# untitled.net
KiCad netlist of a schematic drawn in EAGLE
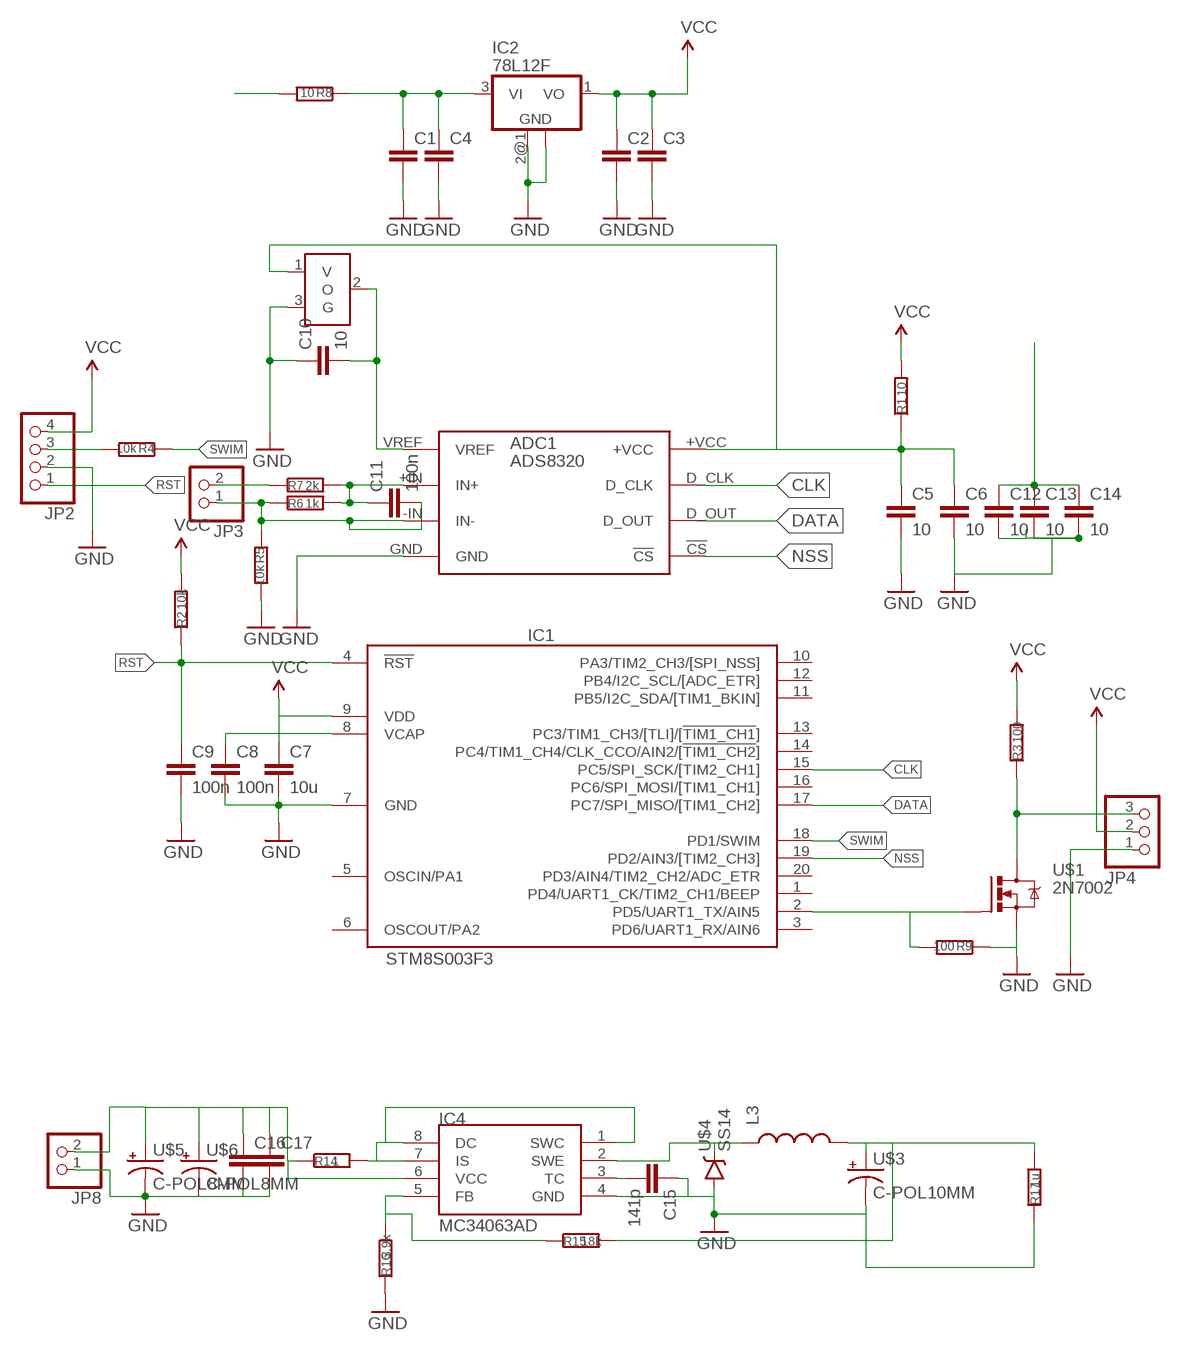
[diagram p0: schematic, sheet 1]

(export (version "E")
  (design (tool "Eeschema 10.0.6"))
  (components
    (comp (ref "ADC1")
      (value "ADS8320")
      (footprint "eagle-import:S-PDSO-G8")
      (libsource (lib "eagle-import") (part "ADS8320"))
    )
    (comp (ref "C1")
      (value "CC0805")
      (footprint "eagle-import:C0805")
      (libsource (lib "eagle-import") (part "CC0805"))
    )
    (comp (ref "C2")
      (value "CC0805")
      (footprint "eagle-import:C0805")
      (libsource (lib "eagle-import") (part "CC0805"))
    )
    (comp (ref "C3")
      (value "CC0805")
      (footprint "eagle-import:C0805")
      (libsource (lib "eagle-import") (part "CC0805"))
    )
    (comp (ref "C4")
      (value "CC0805")
      (footprint "eagle-import:C0805")
      (libsource (lib "eagle-import") (part "CC0805"))
    )
    (comp (ref "C5")
      (value "10")
      (footprint "eagle-import:C0805")
      (libsource (lib "eagle-import") (part "CC0805"))
    )
    (comp (ref "C6")
      (value "10")
      (footprint "eagle-import:C0805")
      (libsource (lib "eagle-import") (part "CC0805"))
    )
    (comp (ref "C7")
      (value "10u")
      (footprint "eagle-import:C0805")
      (libsource (lib "eagle-import") (part "CC0805"))
    )
    (comp (ref "C8")
      (value "100n")
      (footprint "eagle-import:C0603")
      (libsource (lib "eagle-import") (part "CC0603"))
    )
    (comp (ref "C9")
      (value "100n")
      (footprint "eagle-import:C0603")
      (libsource (lib "eagle-import") (part "CC0603"))
    )
    (comp (ref "C10")
      (value "10")
      (footprint "eagle-import:C0805")
      (libsource (lib "eagle-import") (part "CC0805"))
    )
    (comp (ref "C11")
      (value "100n")
      (footprint "eagle-import:C0603")
      (libsource (lib "eagle-import") (part "CC0603"))
    )
    (comp (ref "C12")
      (value "10")
      (footprint "eagle-import:C0805")
      (libsource (lib "eagle-import") (part "CC0805"))
    )
    (comp (ref "C13")
      (value "10")
      (footprint "eagle-import:C0805")
      (libsource (lib "eagle-import") (part "CC0805"))
    )
    (comp (ref "C14")
      (value "10")
      (footprint "eagle-import:C0805")
      (libsource (lib "eagle-import") (part "CC0805"))
    )
    (comp (ref "C15")
      (value "141p")
      (footprint "eagle-import:C0603")
      (libsource (lib "eagle-import") (part "CC0603"))
    )
    (comp (ref "C16")
      (value "CC0805")
      (footprint "eagle-import:C0805")
      (libsource (lib "eagle-import") (part "CC0805"))
    )
    (comp (ref "C17")
      (value "CC0805")
      (footprint "eagle-import:C0805")
      (libsource (lib "eagle-import") (part "CC0805"))
    )
    (comp (ref "IC1")
      (value "STM8S003F3")
      (footprint "eagle-import:TSSOP20")
      (libsource (lib "eagle-import") (part "STM8S003F3"))
    )
    (comp (ref "IC2")
      (value "78L12F")
      (footprint "eagle-import:SOT89")
      (libsource (lib "eagle-import") (part "78LF12"))
    )
    (comp (ref "IC4")
      (value "MC34063AD")
      (footprint "eagle-import:SOIC8")
      (libsource (lib "eagle-import") (part "MC34063AD"))
    )
    (comp (ref "JP2")
      (value "PINHD-1X04_2.54")
      (footprint "eagle-import:1X04")
      (libsource (lib "eagle-import") (part "PINHD-1X04_2.54"))
    )
    (comp (ref "JP3")
      (value "PINHD-1X2")
      (footprint "eagle-import:1X02")
      (libsource (lib "eagle-import") (part "PINHD-1X2"))
    )
    (comp (ref "JP4")
      (value "PINHD-1X03_2.54")
      (footprint "eagle-import:1X03")
      (libsource (lib "eagle-import") (part "PINHD-1X03_2.54"))
    )
    (comp (ref "JP8")
      (value "PINHD-1X02_2.54")
      (footprint "eagle-import:1X02")
      (libsource (lib "eagle-import") (part "PINHD-1X02_2.54"))
    )
    (comp (ref "L3")
      (value "INDUCTORSRU1038")
      (footprint "eagle-import:SRU1038")
      (libsource (lib "eagle-import") (part "INDUCTORSRU1038"))
    )
    (comp (ref "R1")
      (value "10")
      (footprint "eagle-import:0603")
      (libsource (lib "eagle-import") (part "R0603"))
    )
    (comp (ref "R2")
      (value "10k")
      (footprint "eagle-import:0603")
      (libsource (lib "eagle-import") (part "R0603"))
    )
    (comp (ref "R3")
      (value "100")
      (footprint "eagle-import:0603")
      (libsource (lib "eagle-import") (part "R0603"))
    )
    (comp (ref "R4")
      (value "10k")
      (footprint "eagle-import:0603")
      (libsource (lib "eagle-import") (part "R0603"))
    )
    (comp (ref "R5")
      (value "10k")
      (footprint "eagle-import:0603")
      (libsource (lib "eagle-import") (part "R0603"))
    )
    (comp (ref "R6")
      (value "1k")
      (footprint "eagle-import:0603")
      (libsource (lib "eagle-import") (part "R0603"))
    )
    (comp (ref "R7")
      (value "2k")
      (footprint "eagle-import:0603")
      (libsource (lib "eagle-import") (part "R0603"))
    )
    (comp (ref "R8")
      (value "10")
      (footprint "eagle-import:0603")
      (libsource (lib "eagle-import") (part "R0603"))
    )
    (comp (ref "R9")
      (value "100")
      (footprint "eagle-import:0603")
      (libsource (lib "eagle-import") (part "R0603"))
    )
    (comp (ref "R14")
      (value "1")
      (footprint "eagle-import:R0805")
      (libsource (lib "eagle-import") (part "R0805"))
    )
    (comp (ref "R15")
      (value "18k")
      (footprint "eagle-import:0603")
      (libsource (lib "eagle-import") (part "R0603"))
    )
    (comp (ref "R16")
      (value "3.9k")
      (footprint "eagle-import:0603")
      (libsource (lib "eagle-import") (part "R0603"))
    )
    (comp (ref "R17")
      (value "1u")
      (footprint "eagle-import:R0805")
      (libsource (lib "eagle-import") (part "R0805"))
    )
    (comp (ref "U$1")
      (value "2N7002")
      (footprint "eagle-import:SOT23")
      (libsource (lib "eagle-import") (part "2N7002"))
    )
    (comp (ref "U$2")
      (value "REF3025")
      (footprint "eagle-import:SOT23")
      (libsource (lib "eagle-import") (part "REF3025"))
    )
    (comp (ref "U$3")
      (value "C-POL10MM")
      (footprint "eagle-import:PCAP10")
      (libsource (lib "eagle-import") (part "C-POL10MM"))
    )
    (comp (ref "U$4")
      (value "SS14")
      (footprint "eagle-import:SMA-DIODE")
      (libsource (lib "eagle-import") (part "SS14"))
    )
    (comp (ref "U$5")
      (value "C-POL8MM")
      (footprint "eagle-import:PCAP8")
      (libsource (lib "eagle-import") (part "C-POL8MM"))
    )
    (comp (ref "U$6")
      (value "C-POL8MM")
      (footprint "eagle-import:PCAP8")
      (libsource (lib "eagle-import") (part "C-POL8MM"))
    )
  )
  (nets
    (net (code "1") (name "/N$2") (class "Default")
      (node (ref "C1") (pin "1") (pinfunction "1_1") (pintype "passive"))
      (node (ref "C12") (pin "1") (pinfunction "1_1") (pintype "passive"))
      (node (ref "C13") (pin "1") (pinfunction "1_1") (pintype "passive"))
      (node (ref "C14") (pin "1") (pinfunction "1_1") (pintype "passive"))
      (node (ref "C4") (pin "1") (pinfunction "1_1") (pintype "passive"))
      (node (ref "IC2") (pin "3") (pinfunction "VI_3") (pintype "input"))
      (node (ref "L3") (pin "2") (pinfunction "2_2") (pintype "passive"))
      (node (ref "R15") (pin "2") (pinfunction "2_2") (pintype "passive"))
      (node (ref "R17") (pin "2") (pinfunction "2_2") (pintype "passive"))
      (node (ref "R8") (pin "1") (pinfunction "1_1") (pintype "passive"))
      (node (ref "U$3") (pin "P$1") (pinfunction "+_P$1") (pintype "passive"))
    )
    (net (code "2") (name "CLK") (class "Default")
      (node (ref "ADC1") (pin "D_CLK") (pinfunction "D_CLK_D_CLK") (pintype "input"))
      (node (ref "IC1") (pin "15") (pinfunction "PC5/SPI_SCK/[TIM2_CH1]_15") (pintype "bidirectional"))
    )
    (net (code "3") (name "DATA") (class "Default")
      (node (ref "ADC1") (pin "D_OUT") (pinfunction "D_OUT_D_OUT") (pintype "output"))
      (node (ref "IC1") (pin "17") (pinfunction "PC7/SPI_MISO/[TIM1_CH2]_17") (pintype "bidirectional"))
    )
    (net (code "4") (name "GND") (class "Default")
      (node (ref "ADC1") (pin "GND") (pinfunction "GND_GND") (pintype "power_in"))
      (node (ref "C1") (pin "2") (pinfunction "2_2") (pintype "passive"))
      (node (ref "C10") (pin "1") (pinfunction "1_1") (pintype "passive"))
      (node (ref "C12") (pin "2") (pinfunction "2_2") (pintype "passive"))
      (node (ref "C13") (pin "2") (pinfunction "2_2") (pintype "passive"))
      (node (ref "C14") (pin "2") (pinfunction "2_2") (pintype "passive"))
      (node (ref "C15") (pin "1") (pinfunction "1_1") (pintype "passive"))
      (node (ref "C16") (pin "2") (pinfunction "2_2") (pintype "passive"))
      (node (ref "C17") (pin "2") (pinfunction "2_2") (pintype "passive"))
      (node (ref "C2") (pin "2") (pinfunction "2_2") (pintype "passive"))
      (node (ref "C3") (pin "2") (pinfunction "2_2") (pintype "passive"))
      (node (ref "C4") (pin "2") (pinfunction "2_2") (pintype "passive"))
      (node (ref "C5") (pin "2") (pinfunction "2_2") (pintype "passive"))
      (node (ref "C6") (pin "2") (pinfunction "2_2") (pintype "passive"))
      (node (ref "C7") (pin "2") (pinfunction "2_2") (pintype "passive"))
      (node (ref "C8") (pin "2") (pinfunction "2_2") (pintype "passive"))
      (node (ref "C9") (pin "2") (pinfunction "2_2") (pintype "passive"))
      (node (ref "IC1") (pin "7") (pinfunction "GND_7") (pintype "power_in"))
      (node (ref "IC2") (pin "2") (pinfunction "GND_2") (pintype "passive"))
      (node (ref "IC2") (pin "2@1") (pinfunction "GND_2@1") (pintype "passive"))
      (node (ref "IC4") (pin "4") (pinfunction "GND_4") (pintype "passive"))
      (node (ref "JP2") (pin "2") (pinfunction "2_2") (pintype "passive"))
      (node (ref "JP4") (pin "1") (pinfunction "1_1") (pintype "passive"))
      (node (ref "JP8") (pin "1") (pinfunction "1_1") (pintype "passive"))
      (node (ref "R16") (pin "1") (pinfunction "1_1") (pintype "passive"))
      (node (ref "R17") (pin "1") (pinfunction "1_1") (pintype "passive"))
      (node (ref "R5") (pin "2") (pinfunction "2_2") (pintype "passive"))
      (node (ref "R9") (pin "1") (pinfunction "1_1") (pintype "passive"))
      (node (ref "U$1") (pin "2") (pinfunction "S_2") (pintype "passive"))
      (node (ref "U$2") (pin "3") (pinfunction "G_3") (pintype "bidirectional"))
      (node (ref "U$3") (pin "P$2") (pinfunction "-_P$2") (pintype "passive"))
      (node (ref "U$4") (pin "A") (pinfunction "A_A") (pintype "passive"))
      (node (ref "U$5") (pin "P$2") (pinfunction "-_P$2") (pintype "passive"))
      (node (ref "U$6") (pin "P$2") (pinfunction "-_P$2") (pintype "passive"))
    )
    (net (code "5") (name "NSS") (class "Default")
      (node (ref "ADC1") (pin "!CS") (pinfunction "~{CS}_!CS") (pintype "input"))
      (node (ref "IC1") (pin "19") (pinfunction "PD2/AIN3/[TIM2_CH3]_19") (pintype "bidirectional"))
    )
    (net (code "6") (name "Net-(ADC1-IN+)") (class "Default")
      (node (ref "ADC1") (pin "+IN") (pinfunction "IN+_+IN") (pintype "input"))
      (node (ref "C11") (pin "1") (pinfunction "1_1") (pintype "passive"))
      (node (ref "R6") (pin "2") (pinfunction "2_2") (pintype "passive"))
      (node (ref "R7") (pin "2") (pinfunction "2_2") (pintype "passive"))
    )
    (net (code "7") (name "Net-(ADC1-IN-)") (class "Default")
      (node (ref "ADC1") (pin "-IN") (pinfunction "IN-_-IN") (pintype "input"))
      (node (ref "C11") (pin "2") (pinfunction "2_2") (pintype "passive"))
      (node (ref "JP3") (pin "1") (pinfunction "1_1") (pintype "passive"))
      (node (ref "R5") (pin "1") (pinfunction "1_1") (pintype "passive"))
      (node (ref "R6") (pin "1") (pinfunction "1_1") (pintype "passive"))
    )
    (net (code "8") (name "Net-(IC1-PD5{slash}UART1_TX{slash}AIN5)") (class "Default")
      (node (ref "IC1") (pin "2") (pinfunction "PD5/UART1_TX/AIN5_2") (pintype "bidirectional"))
      (node (ref "R9") (pin "2") (pinfunction "2_2") (pintype "passive"))
      (node (ref "U$1") (pin "1") (pinfunction "G_1") (pintype "passive"))
    )
    (net (code "9") (name "Net-(IC1-VCAP)") (class "Default")
      (node (ref "C8") (pin "1") (pinfunction "1_1") (pintype "passive"))
      (node (ref "IC1") (pin "8") (pinfunction "VCAP_8") (pintype "power_in"))
    )
    (net (code "10") (name "Net-(IC4-DC)") (class "Default")
      (node (ref "IC4") (pin "1") (pinfunction "SWC_1") (pintype "passive"))
      (node (ref "IC4") (pin "7") (pinfunction "IS_7") (pintype "passive"))
      (node (ref "IC4") (pin "8") (pinfunction "DC_8") (pintype "passive"))
      (node (ref "R14") (pin "2") (pinfunction "2_2") (pintype "passive"))
    )
    (net (code "11") (name "Net-(IC4-FB)") (class "Default")
      (node (ref "IC4") (pin "5") (pinfunction "FB_5") (pintype "passive"))
      (node (ref "R15") (pin "1") (pinfunction "1_1") (pintype "passive"))
      (node (ref "R16") (pin "2") (pinfunction "2_2") (pintype "passive"))
    )
    (net (code "12") (name "Net-(IC4-SWE)") (class "Default")
      (node (ref "IC4") (pin "2") (pinfunction "SWE_2") (pintype "passive"))
      (node (ref "L3") (pin "1") (pinfunction "1_1") (pintype "passive"))
      (node (ref "U$4") (pin "C") (pinfunction "C_C") (pintype "passive"))
    )
    (net (code "13") (name "Net-(IC4-TC)") (class "Default")
      (node (ref "C15") (pin "2") (pinfunction "2_2") (pintype "passive"))
      (node (ref "IC4") (pin "3") (pinfunction "TC_3") (pintype "passive"))
    )
    (net (code "14") (name "Net-(IC4-VCC)") (class "Default")
      (node (ref "C16") (pin "1") (pinfunction "1_1") (pintype "passive"))
      (node (ref "C17") (pin "1") (pinfunction "1_1") (pintype "passive"))
      (node (ref "IC4") (pin "6") (pinfunction "VCC_6") (pintype "passive"))
      (node (ref "JP8") (pin "2") (pinfunction "2_2") (pintype "passive"))
      (node (ref "R14") (pin "1") (pinfunction "1_1") (pintype "passive"))
      (node (ref "U$5") (pin "P$1") (pinfunction "+_P$1") (pintype "passive"))
      (node (ref "U$6") (pin "P$1") (pinfunction "+_P$1") (pintype "passive"))
    )
    (net (code "15") (name "Net-(JP2-Pad3)") (class "Default")
      (node (ref "JP2") (pin "3") (pinfunction "3_3") (pintype "passive"))
      (node (ref "R4") (pin "2") (pinfunction "2_2") (pintype "passive"))
    )
    (net (code "16") (name "Net-(JP3-Pad2)") (class "Default")
      (node (ref "JP3") (pin "2") (pinfunction "2_2") (pintype "passive"))
      (node (ref "R7") (pin "1") (pinfunction "1_1") (pintype "passive"))
    )
    (net (code "17") (name "Net-(U$1-D)") (class "Default")
      (node (ref "JP4") (pin "3") (pinfunction "3_3") (pintype "passive"))
      (node (ref "R3") (pin "1") (pinfunction "1_1") (pintype "passive"))
      (node (ref "U$1") (pin "3") (pinfunction "D_3") (pintype "passive"))
    )
    (net (code "18") (name "Net-(U$2-O)") (class "Default")
      (node (ref "ADC1") (pin "VREF") (pinfunction "VREF_VREF") (pintype "input"))
      (node (ref "C10") (pin "2") (pinfunction "2_2") (pintype "passive"))
      (node (ref "U$2") (pin "2") (pinfunction "O_2") (pintype "bidirectional"))
    )
    (net (code "19") (name "Net-(U$2-V)") (class "Default")
      (node (ref "ADC1") (pin "+VCC") (pinfunction "+VCC_+VCC") (pintype "power_in"))
      (node (ref "C5") (pin "1") (pinfunction "1_1") (pintype "passive"))
      (node (ref "C6") (pin "1") (pinfunction "1_1") (pintype "passive"))
      (node (ref "R1") (pin "1") (pinfunction "1_1") (pintype "passive"))
      (node (ref "U$2") (pin "1") (pinfunction "V_1") (pintype "bidirectional"))
    )
    (net (code "20") (name "RST") (class "Default")
      (node (ref "C9") (pin "1") (pinfunction "1_1") (pintype "passive"))
      (node (ref "IC1") (pin "4") (pinfunction "~{RST}_4") (pintype "input"))
      (node (ref "JP2") (pin "1") (pinfunction "1_1") (pintype "passive"))
      (node (ref "R2") (pin "1") (pinfunction "1_1") (pintype "passive"))
    )
    (net (code "21") (name "SWIM") (class "Default")
      (node (ref "IC1") (pin "18") (pinfunction "PD1/SWIM_18") (pintype "bidirectional"))
      (node (ref "R4") (pin "1") (pinfunction "1_1") (pintype "passive"))
    )
    (net (code "22") (name "VCC") (class "Default")
      (node (ref "C2") (pin "1") (pinfunction "1_1") (pintype "passive"))
      (node (ref "C3") (pin "1") (pinfunction "1_1") (pintype "passive"))
      (node (ref "C7") (pin "1") (pinfunction "1_1") (pintype "passive"))
      (node (ref "IC1") (pin "9") (pinfunction "VDD_9") (pintype "power_in"))
      (node (ref "IC2") (pin "1") (pinfunction "VO_1") (pintype "passive"))
      (node (ref "JP2") (pin "4") (pinfunction "4_4") (pintype "passive"))
      (node (ref "JP4") (pin "2") (pinfunction "2_2") (pintype "passive"))
      (node (ref "R1") (pin "2") (pinfunction "2_2") (pintype "passive"))
      (node (ref "R2") (pin "2") (pinfunction "2_2") (pintype "passive"))
      (node (ref "R3") (pin "2") (pinfunction "2_2") (pintype "passive"))
    )
    (net (code "23") (name "unconnected-(IC1-OSCIN{slash}PA1-Pad5)") (class "Default")
      (node (ref "IC1") (pin "5") (pinfunction "OSCIN/PA1_5") (pintype "bidirectional"))
    )
    (net (code "24") (name "unconnected-(IC1-OSCOUT{slash}PA2-Pad6)") (class "Default")
      (node (ref "IC1") (pin "6") (pinfunction "OSCOUT/PA2_6") (pintype "bidirectional"))
    )
    (net (code "25") (name "unconnected-(IC1-PA3{slash}TIM2_CH3{slash}[SPI_NSS]-Pad10)") (class "Default")
      (node (ref "IC1") (pin "10") (pinfunction "PA3/TIM2_CH3/[SPI_NSS]_10") (pintype "bidirectional"))
    )
    (net (code "26") (name "unconnected-(IC1-PB4{slash}I2C_SCL{slash}[ADC_ETR]-Pad12)") (class "Default")
      (node (ref "IC1") (pin "12") (pinfunction "PB4/I2C_SCL/[ADC_ETR]_12") (pintype "bidirectional"))
    )
    (net (code "27") (name "unconnected-(IC1-PB5{slash}I2C_SDA{slash}[TIM1_BKIN]-Pad11)") (class "Default")
      (node (ref "IC1") (pin "11") (pinfunction "PB5/I2C_SDA/[TIM1_BKIN]_11") (pintype "bidirectional"))
    )
    (net (code "28") (name "unconnected-(IC1-PC3{slash}TIM1_CH3{slash}[TLI]{slash}[~{TIM1_CH1}]-Pad13)") (class "Default")
      (node (ref "IC1") (pin "13") (pinfunction "PC3/TIM1_CH3/[TLI]/[~{TIM1_CH1}]_13") (pintype "bidirectional"))
    )
    (net (code "29") (name "unconnected-(IC1-PC4{slash}TIM1_CH4{slash}CLK_CCO{slash}AIN2{slash}[~{TIM1_CH2}]-Pad14)") (class "Default")
      (node (ref "IC1") (pin "14") (pinfunction "PC4/TIM1_CH4/CLK_CCO/AIN2/[~{TIM1_CH2}]_14") (pintype "bidirectional"))
    )
    (net (code "30") (name "unconnected-(IC1-PC6{slash}SPI_MOSI{slash}[TIM1_CH1]-Pad16)") (class "Default")
      (node (ref "IC1") (pin "16") (pinfunction "PC6/SPI_MOSI/[TIM1_CH1]_16") (pintype "bidirectional"))
    )
    (net (code "31") (name "unconnected-(IC1-PD3{slash}AIN4{slash}TIM2_CH2{slash}ADC_ETR-Pad20)") (class "Default")
      (node (ref "IC1") (pin "20") (pinfunction "PD3/AIN4/TIM2_CH2/ADC_ETR_20") (pintype "bidirectional"))
    )
    (net (code "32") (name "unconnected-(IC1-PD4{slash}UART1_CK{slash}TIM2_CH1{slash}BEEP-Pad1)") (class "Default")
      (node (ref "IC1") (pin "1") (pinfunction "PD4/UART1_CK/TIM2_CH1/BEEP_1") (pintype "bidirectional"))
    )
    (net (code "33") (name "unconnected-(IC1-PD6{slash}UART1_RX{slash}AIN6-Pad3)") (class "Default")
      (node (ref "IC1") (pin "3") (pinfunction "PD6/UART1_RX/AIN6_3") (pintype "bidirectional"))
    )
    (net (code "34") (name "unconnected-(R8-Pad2)") (class "Default")
      (node (ref "R8") (pin "2") (pinfunction "2_2") (pintype "passive"))
    )
  )
)
